# vote_box.net
KiCad netlist of a schematic drawn in EAGLE
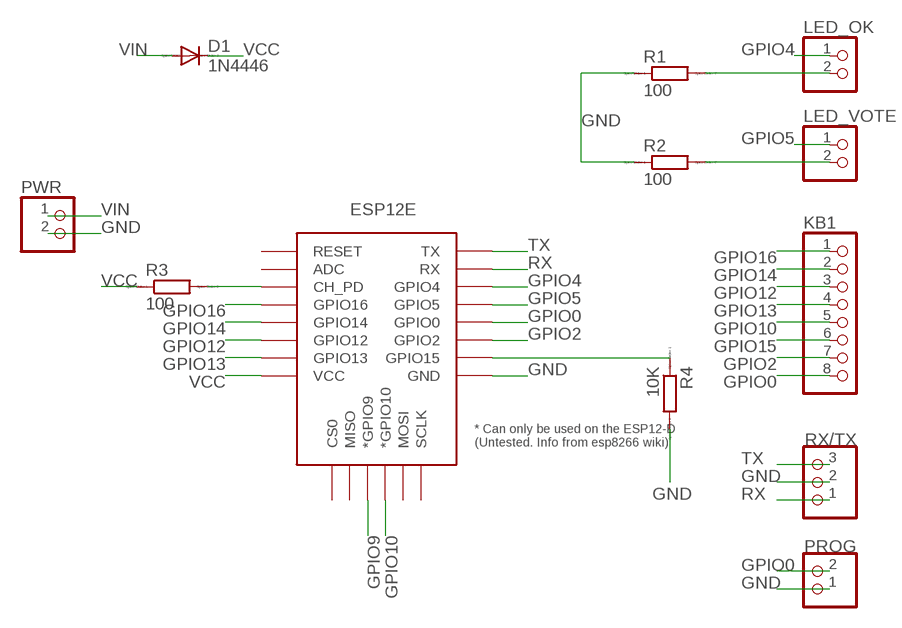
[diagram p0: schematic, sheet 1]

(export (version "E")
  (design (tool "Eeschema 10.0.6"))
  (components
    (comp (ref "D1")
      (value "1N4446")
      (footprint "eagle-import:DO35-10")
      (libsource (lib "eagle-import") (part "1N4446"))
    )
    (comp (ref "ESP12E")
      (value "ESP12ESMD")
      (footprint "eagle-import:ESP12E-SMD")
      (libsource (lib "eagle-import") (part "ESP12ESMD"))
    )
    (comp (ref "KB1")
      (value "PINHD-1X8")
      (footprint "eagle-import:1X08")
      (libsource (lib "eagle-import") (part "PINHD-1X8"))
    )
    (comp (ref "LED_OK")
      (value "PINHD-1X2")
      (footprint "eagle-import:1X02")
      (libsource (lib "eagle-import") (part "PINHD-1X2"))
    )
    (comp (ref "LED_VOTE")
      (value "PINHD-1X2")
      (footprint "eagle-import:1X02")
      (libsource (lib "eagle-import") (part "PINHD-1X2"))
    )
    (comp (ref "PROG")
      (value "PINHD-1X2")
      (footprint "eagle-import:1X02")
      (libsource (lib "eagle-import") (part "PINHD-1X2"))
    )
    (comp (ref "PWR")
      (value "PINHD-1X2")
      (footprint "eagle-import:1X02")
      (libsource (lib "eagle-import") (part "PINHD-1X2"))
    )
    (comp (ref "R1")
      (value "100")
      (footprint "eagle-import:0207_10")
      (libsource (lib "eagle-import") (part "R0207/10"))
    )
    (comp (ref "R2")
      (value "100")
      (footprint "eagle-import:0207_10")
      (libsource (lib "eagle-import") (part "R0207/10"))
    )
    (comp (ref "R3")
      (value "100")
      (footprint "eagle-import:0207_10")
      (libsource (lib "eagle-import") (part "R0207/10"))
    )
    (comp (ref "R4")
      (value "10K")
      (footprint "eagle-import:0207_10")
      (libsource (lib "eagle-import") (part "R0207/10"))
    )
    (comp (ref "RX/TX")
      (value "PINHD-1X3")
      (footprint "eagle-import:1X03")
      (libsource (lib "eagle-import") (part "PINHD-1X3"))
    )
  )
  (nets
    (net (code "1") (name "/GND") (class "Default")
      (node (ref "ESP12E") (pin "GND") (pinfunction "GND_GND") (pintype "bidirectional"))
      (node (ref "PROG") (pin "1") (pinfunction "1_1") (pintype "passive"))
      (node (ref "PWR") (pin "2") (pinfunction "2_2") (pintype "passive"))
      (node (ref "R1") (pin "1") (pinfunction "1_1") (pintype "passive"))
      (node (ref "R2") (pin "1") (pinfunction "1_1") (pintype "passive"))
      (node (ref "R4") (pin "2") (pinfunction "2_2") (pintype "passive"))
      (node (ref "RX/TX") (pin "2") (pinfunction "2_2") (pintype "passive"))
    )
    (net (code "2") (name "/GPIO0") (class "Default")
      (node (ref "ESP12E") (pin "GPIO0") (pinfunction "GPIO0_GPIO0") (pintype "bidirectional"))
      (node (ref "KB1") (pin "8") (pinfunction "8_8") (pintype "passive"))
      (node (ref "PROG") (pin "2") (pinfunction "2_2") (pintype "passive"))
    )
    (net (code "3") (name "/GPIO2") (class "Default")
      (node (ref "ESP12E") (pin "GPIO2") (pinfunction "GPIO2_GPIO2") (pintype "bidirectional"))
      (node (ref "KB1") (pin "7") (pinfunction "7_7") (pintype "passive"))
    )
    (net (code "4") (name "/GPIO4") (class "Default")
      (node (ref "ESP12E") (pin "GPIO4") (pinfunction "GPIO4_GPIO4") (pintype "bidirectional"))
      (node (ref "LED_OK") (pin "1") (pinfunction "1_1") (pintype "passive"))
    )
    (net (code "5") (name "/GPIO5") (class "Default")
      (node (ref "ESP12E") (pin "GPIO5") (pinfunction "GPIO5_GPIO5") (pintype "bidirectional"))
      (node (ref "LED_VOTE") (pin "1") (pinfunction "1_1") (pintype "passive"))
    )
    (net (code "6") (name "/GPIO9") (class "Default")
      (node (ref "ESP12E") (pin "GPIO9") (pinfunction "*GPIO9_GPIO9") (pintype "bidirectional"))
    )
    (net (code "7") (name "/GPIO10") (class "Default")
      (node (ref "ESP12E") (pin "GPIO10") (pinfunction "*GPIO10_GPIO10") (pintype "bidirectional"))
      (node (ref "KB1") (pin "5") (pinfunction "5_5") (pintype "passive"))
    )
    (net (code "8") (name "/GPIO12") (class "Default")
      (node (ref "ESP12E") (pin "GPIO12") (pinfunction "GPIO12_GPIO12") (pintype "bidirectional"))
      (node (ref "KB1") (pin "3") (pinfunction "3_3") (pintype "passive"))
    )
    (net (code "9") (name "/GPIO13") (class "Default")
      (node (ref "ESP12E") (pin "GPIO13") (pinfunction "GPIO13_GPIO13") (pintype "bidirectional"))
      (node (ref "KB1") (pin "4") (pinfunction "4_4") (pintype "passive"))
    )
    (net (code "10") (name "/GPIO14") (class "Default")
      (node (ref "ESP12E") (pin "GPIO14") (pinfunction "GPIO14_GPIO14") (pintype "bidirectional"))
      (node (ref "KB1") (pin "2") (pinfunction "2_2") (pintype "passive"))
    )
    (net (code "11") (name "/GPIO15") (class "Default")
      (node (ref "ESP12E") (pin "GPIO15") (pinfunction "GPIO15_GPIO15") (pintype "bidirectional"))
      (node (ref "KB1") (pin "6") (pinfunction "6_6") (pintype "passive"))
      (node (ref "R4") (pin "1") (pinfunction "1_1") (pintype "passive"))
    )
    (net (code "12") (name "/GPIO16") (class "Default")
      (node (ref "ESP12E") (pin "GPIO16") (pinfunction "GPIO16_GPIO16") (pintype "bidirectional"))
      (node (ref "KB1") (pin "1") (pinfunction "1_1") (pintype "passive"))
    )
    (net (code "13") (name "/RX") (class "Default")
      (node (ref "ESP12E") (pin "RXD0") (pinfunction "RX_RXD0") (pintype "bidirectional"))
      (node (ref "RX/TX") (pin "1") (pinfunction "1_1") (pintype "passive"))
    )
    (net (code "14") (name "/TX") (class "Default")
      (node (ref "ESP12E") (pin "TXD0") (pinfunction "TX_TXD0") (pintype "bidirectional"))
      (node (ref "RX/TX") (pin "3") (pinfunction "3_3") (pintype "passive"))
    )
    (net (code "15") (name "/VCC") (class "Default")
      (node (ref "D1") (pin "C") (pinfunction "C_C") (pintype "passive"))
      (node (ref "ESP12E") (pin "VCC") (pinfunction "VCC_VCC") (pintype "bidirectional"))
      (node (ref "R3") (pin "1") (pinfunction "1_1") (pintype "passive"))
    )
    (net (code "16") (name "/VIN") (class "Default")
      (node (ref "D1") (pin "A") (pinfunction "A_A") (pintype "passive"))
      (node (ref "PWR") (pin "1") (pinfunction "1_1") (pintype "passive"))
    )
    (net (code "17") (name "Net-(ESP12E-PadCH_PD)") (class "Default")
      (node (ref "ESP12E") (pin "CH_PD") (pinfunction "CH_PD_CH_PD") (pintype "bidirectional"))
      (node (ref "R3") (pin "2") (pinfunction "2_2") (pintype "passive"))
    )
    (net (code "18") (name "Net-(LED_OK-Pad2)") (class "Default")
      (node (ref "LED_OK") (pin "2") (pinfunction "2_2") (pintype "passive"))
      (node (ref "R1") (pin "2") (pinfunction "2_2") (pintype "passive"))
    )
    (net (code "19") (name "Net-(LED_VOTE-Pad2)") (class "Default")
      (node (ref "LED_VOTE") (pin "2") (pinfunction "2_2") (pintype "passive"))
      (node (ref "R2") (pin "2") (pinfunction "2_2") (pintype "passive"))
    )
    (net (code "20") (name "unconnected-(ESP12E-PadADC)") (class "Default")
      (node (ref "ESP12E") (pin "ADC") (pinfunction "ADC_ADC") (pintype "bidirectional"))
    )
    (net (code "21") (name "unconnected-(ESP12E-PadCS0)") (class "Default")
      (node (ref "ESP12E") (pin "CS0") (pinfunction "CS0_CS0") (pintype "bidirectional"))
    )
    (net (code "22") (name "unconnected-(ESP12E-PadMISO)") (class "Default")
      (node (ref "ESP12E") (pin "MISO") (pinfunction "MISO_MISO") (pintype "bidirectional"))
    )
    (net (code "23") (name "unconnected-(ESP12E-PadMOSI)") (class "Default")
      (node (ref "ESP12E") (pin "MOSI") (pinfunction "MOSI_MOSI") (pintype "bidirectional"))
    )
    (net (code "24") (name "unconnected-(ESP12E-PadRESET)") (class "Default")
      (node (ref "ESP12E") (pin "RESET") (pinfunction "RESET_RESET") (pintype "bidirectional"))
    )
    (net (code "25") (name "unconnected-(ESP12E-PadSCLK)") (class "Default")
      (node (ref "ESP12E") (pin "SCLK") (pinfunction "SCLK_SCLK") (pintype "bidirectional"))
    )
  )
)
